# schematic.net
KiCad netlist of a schematic drawn in EAGLE
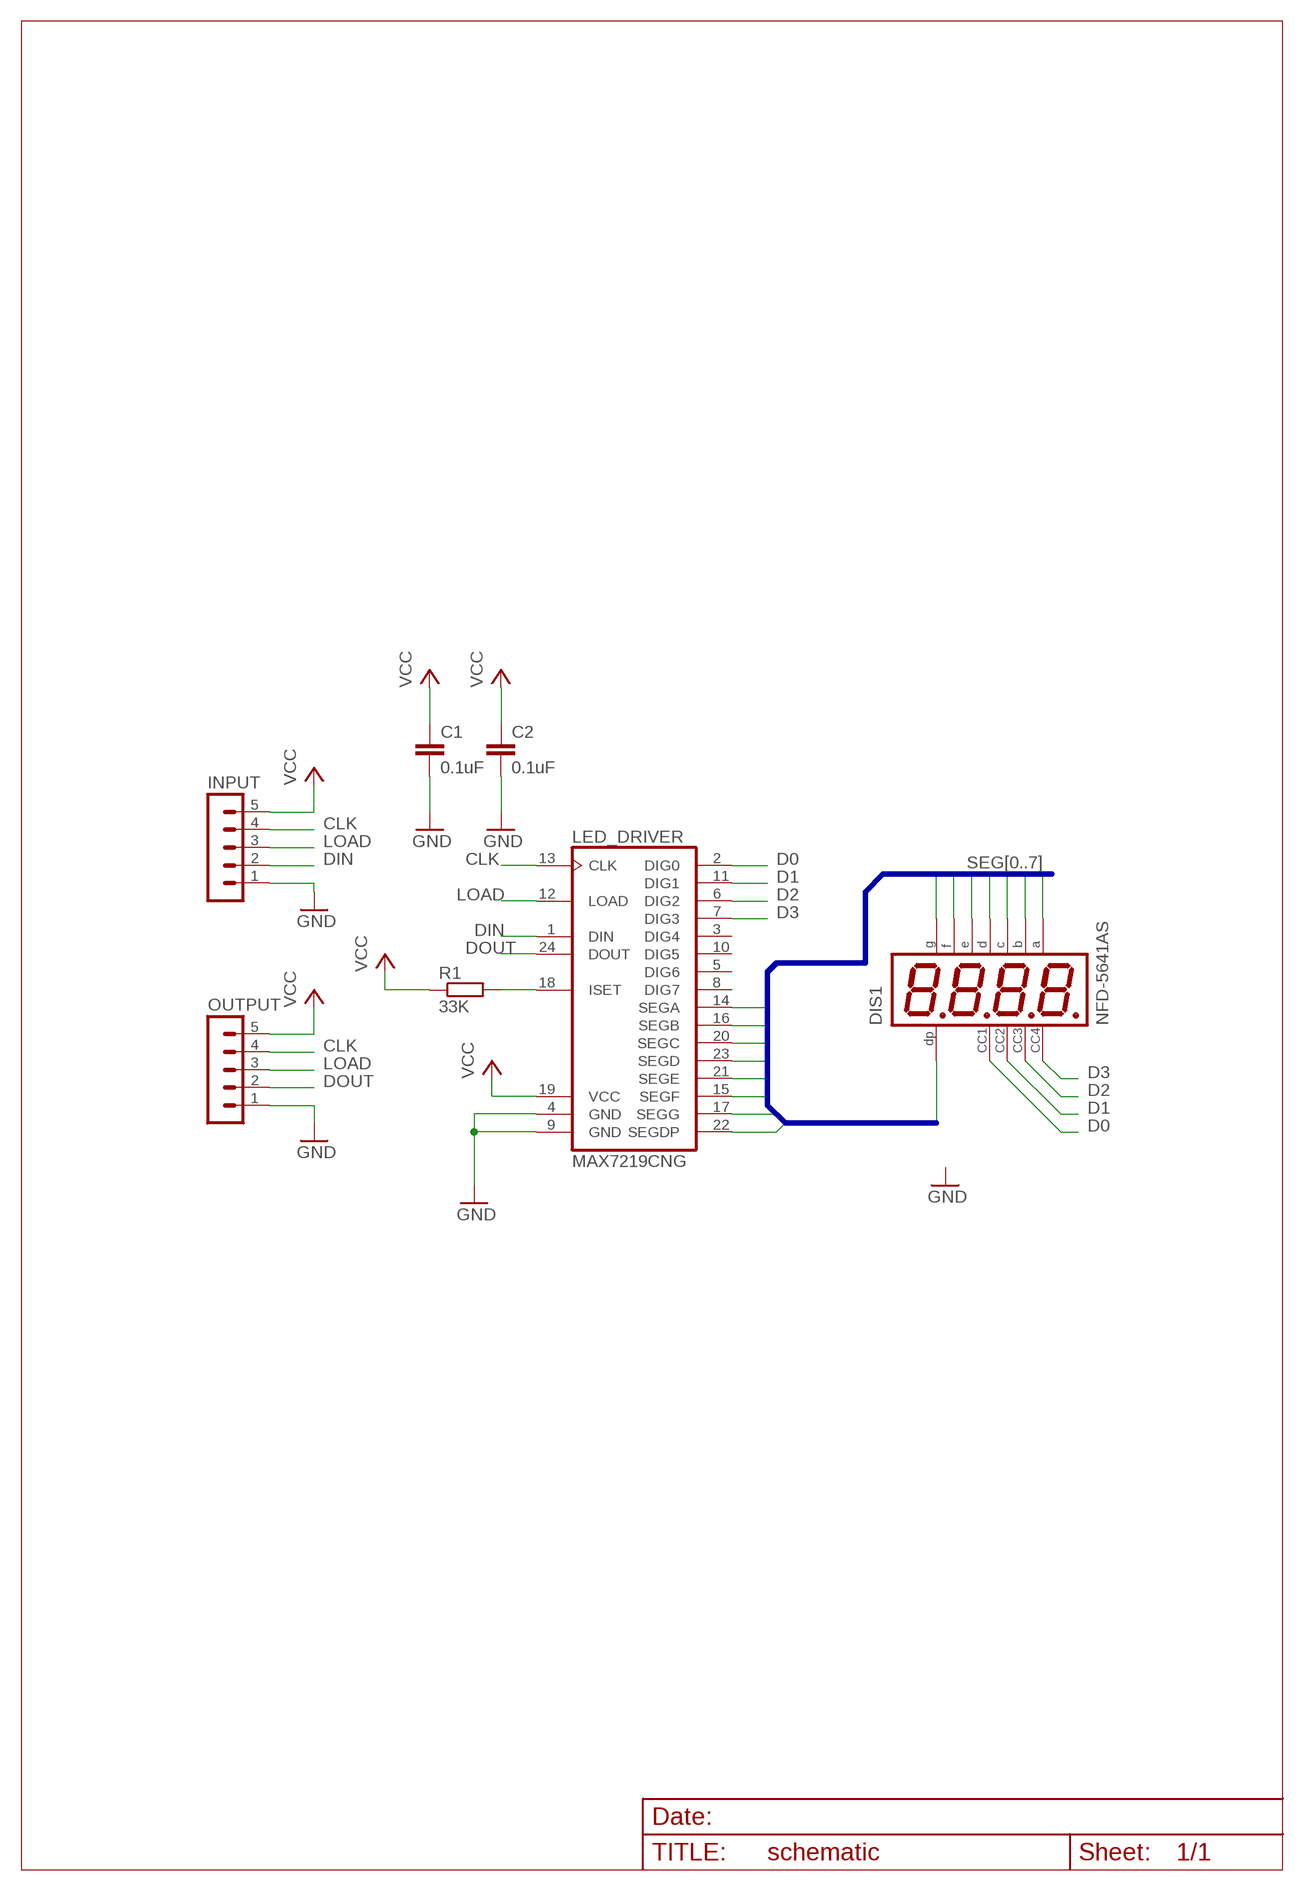
[diagram p0: schematic, sheet 1]

(export (version "E")
  (design (tool "Eeschema 10.0.6"))
  (components
    (comp (ref "C1")
      (value "0.1uF")
      (footprint "eagle-import:C025-025X050")
      (libsource (lib "eagle-import") (part "C-EU025-025X050"))
    )
    (comp (ref "C2")
      (value "0.1uF")
      (footprint "eagle-import:C025-025X050")
      (libsource (lib "eagle-import") (part "C-EU025-025X050"))
    )
    (comp (ref "DIS1")
      (value "NFD-5641AS")
      (footprint "eagle-import:NFD-5641")
      (libsource (lib "eagle-import") (part "NFD-5641AS"))
    )
    (comp (ref "INPUT")
      (value "MA05-1")
      (footprint "eagle-import:MA05-1")
      (libsource (lib "eagle-import") (part "MA05-1"))
    )
    (comp (ref "LED_DRIVER")
      (value "MAX7219CNG")
      (footprint "eagle-import:DIL24-3")
      (fields (field (name "MF") "MAXIM"))
      (libsource (lib "eagle-import") (part "MAX7219CNG"))
    )
    (comp (ref "OUTPUT")
      (value "MA05-1")
      (footprint "eagle-import:MA05-1")
      (libsource (lib "eagle-import") (part "MA05-1"))
    )
    (comp (ref "R1")
      (value "33K")
      (footprint "eagle-import:0207_10")
      (libsource (lib "eagle-import") (part "R-EU_0207/10"))
    )
  )
  (nets
    (net (code "1") (name "/CLK") (class "Default")
      (node (ref "INPUT") (pin "4") (pinfunction "4_4") (pintype "passive"))
      (node (ref "LED_DRIVER") (pin "13") (pinfunction "CLK_13") (pintype "input"))
      (node (ref "OUTPUT") (pin "4") (pinfunction "4_4") (pintype "passive"))
    )
    (net (code "2") (name "/D0") (class "Default")
      (node (ref "DIS1") (pin "P$12") (pinfunction "P$12_P$12") (pintype "bidirectional"))
      (node (ref "LED_DRIVER") (pin "2") (pinfunction "DIG0_2") (pintype "output"))
    )
    (net (code "3") (name "/D1") (class "Default")
      (node (ref "DIS1") (pin "P$9") (pinfunction "P$9_P$9") (pintype "bidirectional"))
      (node (ref "LED_DRIVER") (pin "11") (pinfunction "DIG1_11") (pintype "output"))
    )
    (net (code "4") (name "/D2") (class "Default")
      (node (ref "DIS1") (pin "P$8") (pinfunction "P$8_P$8") (pintype "bidirectional"))
      (node (ref "LED_DRIVER") (pin "6") (pinfunction "DIG2_6") (pintype "output"))
    )
    (net (code "5") (name "/D3") (class "Default")
      (node (ref "DIS1") (pin "P$6") (pinfunction "P$6_P$6") (pintype "bidirectional"))
      (node (ref "LED_DRIVER") (pin "7") (pinfunction "DIG3_7") (pintype "output"))
    )
    (net (code "6") (name "/DIN") (class "Default")
      (node (ref "INPUT") (pin "2") (pinfunction "2_2") (pintype "passive"))
      (node (ref "LED_DRIVER") (pin "1") (pinfunction "DIN_1") (pintype "input"))
    )
    (net (code "7") (name "/DOUT") (class "Default")
      (node (ref "LED_DRIVER") (pin "24") (pinfunction "DOUT_24") (pintype "output"))
      (node (ref "OUTPUT") (pin "2") (pinfunction "2_2") (pintype "passive"))
    )
    (net (code "8") (name "/LOAD") (class "Default")
      (node (ref "INPUT") (pin "3") (pinfunction "3_3") (pintype "passive"))
      (node (ref "LED_DRIVER") (pin "12") (pinfunction "LOAD_12") (pintype "input"))
      (node (ref "OUTPUT") (pin "3") (pinfunction "3_3") (pintype "passive"))
    )
    (net (code "9") (name "/SEG0") (class "Default")
      (node (ref "DIS1") (pin "P$11") (pinfunction "P$11_P$11") (pintype "bidirectional"))
      (node (ref "LED_DRIVER") (pin "14") (pinfunction "SEGA_14") (pintype "output"))
    )
    (net (code "10") (name "/SEG1") (class "Default")
      (node (ref "DIS1") (pin "P$7") (pinfunction "P$7_P$7") (pintype "bidirectional"))
      (node (ref "LED_DRIVER") (pin "16") (pinfunction "SEGB_16") (pintype "output"))
    )
    (net (code "11") (name "/SEG2") (class "Default")
      (node (ref "DIS1") (pin "P$4") (pinfunction "P$4_P$4") (pintype "bidirectional"))
      (node (ref "LED_DRIVER") (pin "20") (pinfunction "SEGC_20") (pintype "output"))
    )
    (net (code "12") (name "/SEG3") (class "Default")
      (node (ref "DIS1") (pin "P$2") (pinfunction "P$2_P$2") (pintype "bidirectional"))
      (node (ref "LED_DRIVER") (pin "23") (pinfunction "SEGD_23") (pintype "output"))
    )
    (net (code "13") (name "/SEG4") (class "Default")
      (node (ref "DIS1") (pin "P$1") (pinfunction "P$1_P$1") (pintype "bidirectional"))
      (node (ref "LED_DRIVER") (pin "21") (pinfunction "SEGE_21") (pintype "output"))
    )
    (net (code "14") (name "/SEG5") (class "Default")
      (node (ref "DIS1") (pin "P$10") (pinfunction "P$10_P$10") (pintype "bidirectional"))
      (node (ref "LED_DRIVER") (pin "15") (pinfunction "SEGF_15") (pintype "output"))
    )
    (net (code "15") (name "/SEG6") (class "Default")
      (node (ref "DIS1") (pin "P$5") (pinfunction "P$5_P$5") (pintype "bidirectional"))
      (node (ref "LED_DRIVER") (pin "17") (pinfunction "SEGG_17") (pintype "output"))
    )
    (net (code "16") (name "/SEG7") (class "Default")
      (node (ref "DIS1") (pin "P$3") (pinfunction "P$3_P$3") (pintype "bidirectional"))
      (node (ref "LED_DRIVER") (pin "22") (pinfunction "SEGDP_22") (pintype "output"))
    )
    (net (code "18") (name "GND") (class "Default")
      (node (ref "C1") (pin "2") (pinfunction "2_2") (pintype "passive"))
      (node (ref "C2") (pin "2") (pinfunction "2_2") (pintype "passive"))
      (node (ref "INPUT") (pin "1") (pinfunction "1_1") (pintype "passive"))
      (node (ref "LED_DRIVER") (pin "4") (pinfunction "GND_4") (pintype "power_in"))
      (node (ref "LED_DRIVER") (pin "9") (pinfunction "GND_9") (pintype "power_in"))
      (node (ref "OUTPUT") (pin "1") (pinfunction "1_1") (pintype "passive"))
    )
    (net (code "19") (name "Net-(LED_DRIVER-ISET)") (class "Default")
      (node (ref "LED_DRIVER") (pin "18") (pinfunction "ISET_18") (pintype "input"))
      (node (ref "R1") (pin "2") (pinfunction "2_2") (pintype "passive"))
    )
    (net (code "20") (name "VCC") (class "Default")
      (node (ref "C1") (pin "1") (pinfunction "1_1") (pintype "passive"))
      (node (ref "C2") (pin "1") (pinfunction "1_1") (pintype "passive"))
      (node (ref "INPUT") (pin "5") (pinfunction "5_5") (pintype "passive"))
      (node (ref "LED_DRIVER") (pin "19") (pinfunction "VCC_19") (pintype "power_in"))
      (node (ref "OUTPUT") (pin "5") (pinfunction "5_5") (pintype "passive"))
      (node (ref "R1") (pin "1") (pinfunction "1_1") (pintype "passive"))
    )
    (net (code "21") (name "unconnected-(LED_DRIVER-DIG4-Pad3)") (class "Default")
      (node (ref "LED_DRIVER") (pin "3") (pinfunction "DIG4_3") (pintype "output"))
    )
    (net (code "22") (name "unconnected-(LED_DRIVER-DIG5-Pad10)") (class "Default")
      (node (ref "LED_DRIVER") (pin "10") (pinfunction "DIG5_10") (pintype "output"))
    )
    (net (code "23") (name "unconnected-(LED_DRIVER-DIG6-Pad5)") (class "Default")
      (node (ref "LED_DRIVER") (pin "5") (pinfunction "DIG6_5") (pintype "output"))
    )
    (net (code "24") (name "unconnected-(LED_DRIVER-DIG7-Pad8)") (class "Default")
      (node (ref "LED_DRIVER") (pin "8") (pinfunction "DIG7_8") (pintype "output"))
    )
  )
)
